# ws2812-attiny.net
KiCad netlist of a schematic drawn in EAGLE
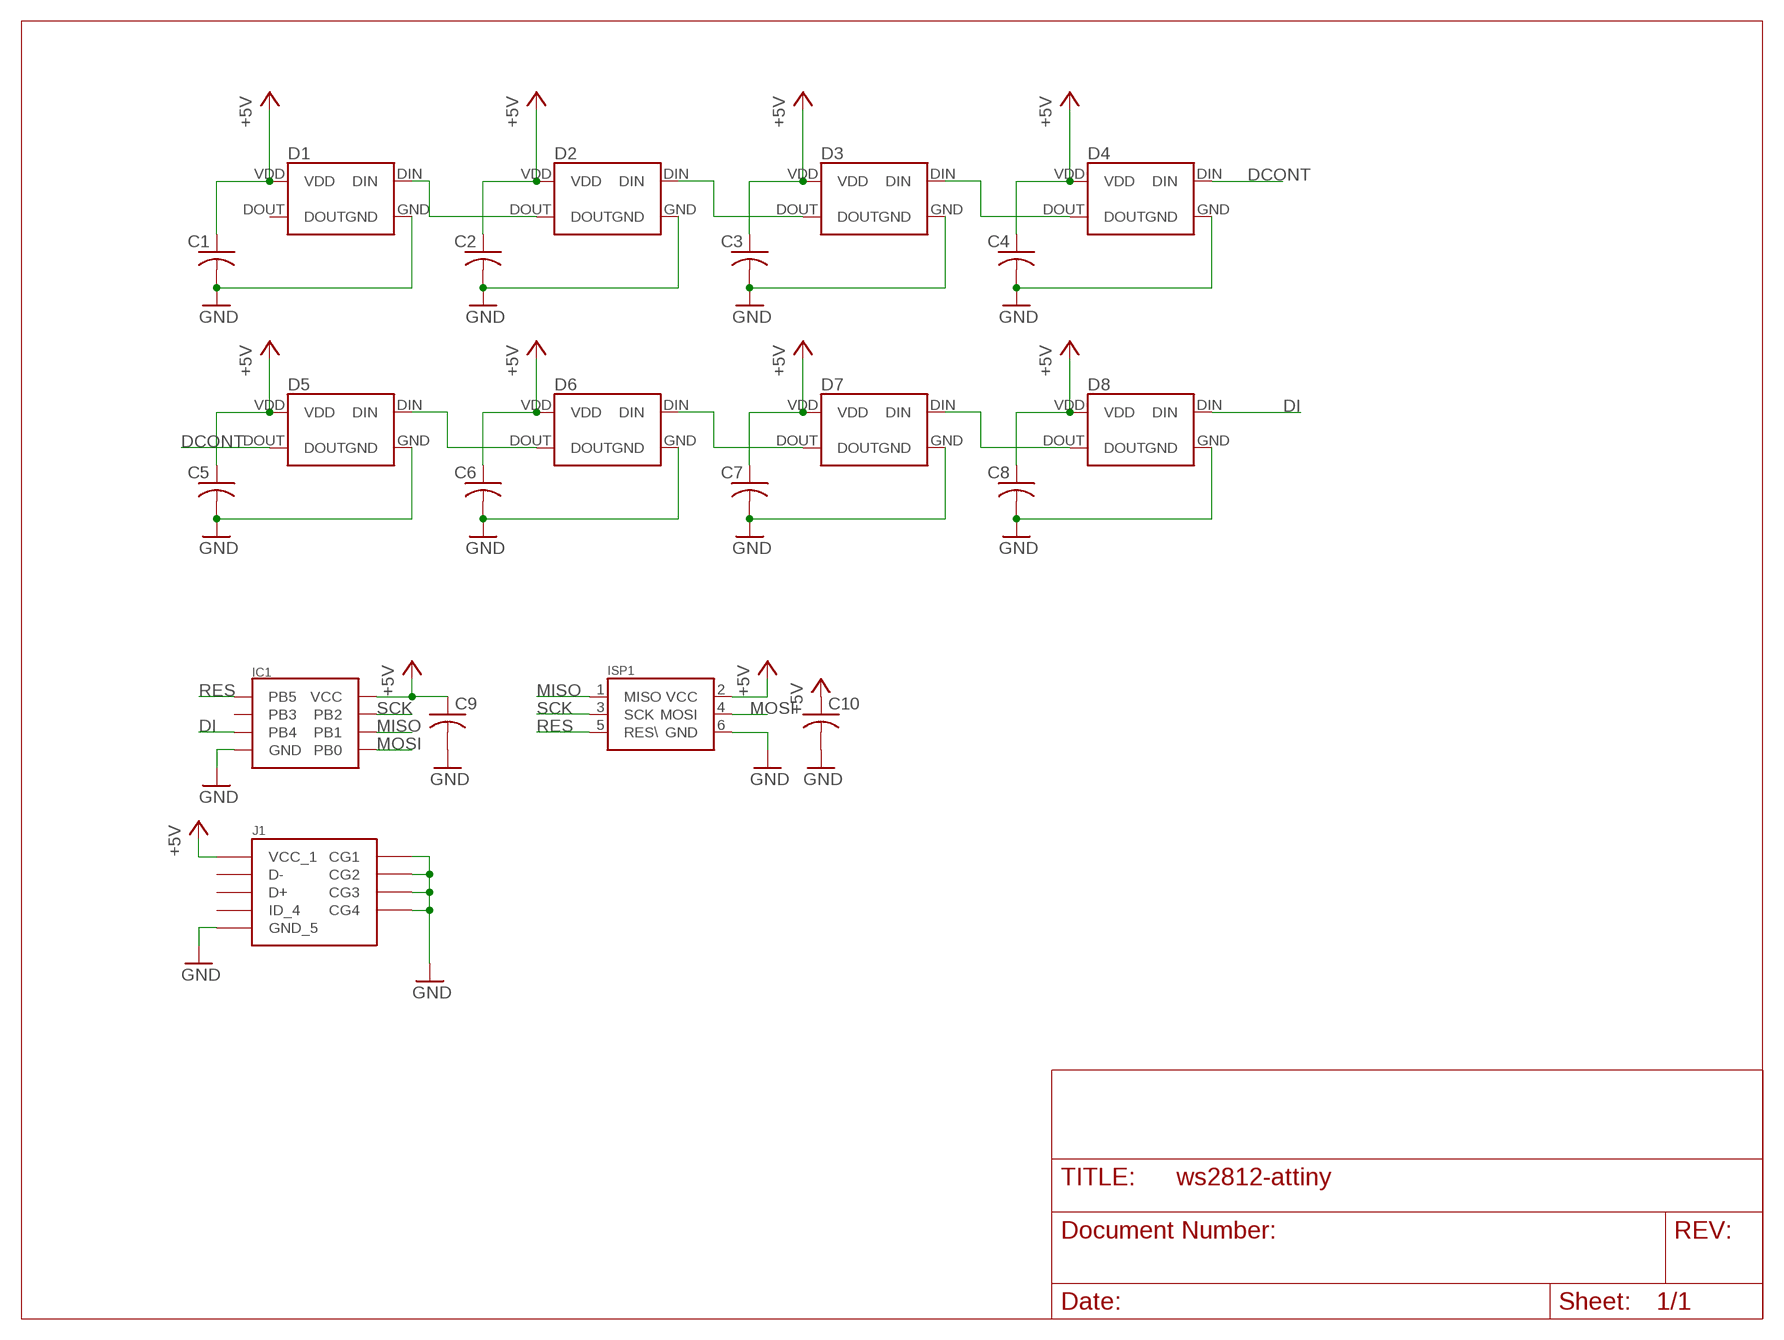
[diagram p0: schematic, sheet 1]

(export (version "E")
  (design (tool "Eeschema 10.0.6"))
  (components
    (comp (ref "C1")
      (value "C-USC1206")
      (footprint "eagle-import:C1206")
      (libsource (lib "eagle-import") (part "C-USC1206"))
    )
    (comp (ref "C2")
      (value "C-USC1206")
      (footprint "eagle-import:C1206")
      (libsource (lib "eagle-import") (part "C-USC1206"))
    )
    (comp (ref "C3")
      (value "C-USC1206")
      (footprint "eagle-import:C1206")
      (libsource (lib "eagle-import") (part "C-USC1206"))
    )
    (comp (ref "C4")
      (value "C-USC1206")
      (footprint "eagle-import:C1206")
      (libsource (lib "eagle-import") (part "C-USC1206"))
    )
    (comp (ref "C5")
      (value "C-USC1206")
      (footprint "eagle-import:C1206")
      (libsource (lib "eagle-import") (part "C-USC1206"))
    )
    (comp (ref "C6")
      (value "C-USC1206")
      (footprint "eagle-import:C1206")
      (libsource (lib "eagle-import") (part "C-USC1206"))
    )
    (comp (ref "C7")
      (value "C-USC1206")
      (footprint "eagle-import:C1206")
      (libsource (lib "eagle-import") (part "C-USC1206"))
    )
    (comp (ref "C8")
      (value "C-USC1206")
      (footprint "eagle-import:C1206")
      (libsource (lib "eagle-import") (part "C-USC1206"))
    )
    (comp (ref "C9")
      (value "C-USC1206")
      (footprint "eagle-import:C1206")
      (libsource (lib "eagle-import") (part "C-USC1206"))
    )
    (comp (ref "C10")
      (value "C-USC1206")
      (footprint "eagle-import:C1206")
      (libsource (lib "eagle-import") (part "C-USC1206"))
    )
    (comp (ref "D1")
      (value "WS2812B")
      (footprint "eagle-import:WS2812B")
      (libsource (lib "eagle-import") (part "WS2812B"))
    )
    (comp (ref "D2")
      (value "WS2812B")
      (footprint "eagle-import:WS2812B")
      (libsource (lib "eagle-import") (part "WS2812B"))
    )
    (comp (ref "D3")
      (value "WS2812B")
      (footprint "eagle-import:WS2812B")
      (libsource (lib "eagle-import") (part "WS2812B"))
    )
    (comp (ref "D4")
      (value "WS2812B")
      (footprint "eagle-import:WS2812B")
      (libsource (lib "eagle-import") (part "WS2812B"))
    )
    (comp (ref "D5")
      (value "WS2812B")
      (footprint "eagle-import:WS2812B")
      (libsource (lib "eagle-import") (part "WS2812B"))
    )
    (comp (ref "D6")
      (value "WS2812B")
      (footprint "eagle-import:WS2812B")
      (libsource (lib "eagle-import") (part "WS2812B"))
    )
    (comp (ref "D7")
      (value "WS2812B")
      (footprint "eagle-import:WS2812B")
      (libsource (lib "eagle-import") (part "WS2812B"))
    )
    (comp (ref "D8")
      (value "WS2812B")
      (footprint "eagle-import:WS2812B")
      (libsource (lib "eagle-import") (part "WS2812B"))
    )
    (comp (ref "IC1")
      (value "ATTINY85")
      (footprint "eagle-import:ATTINY-8S2")
      (libsource (lib "eagle-import") (part "ATTINY85"))
    )
    (comp (ref "ISP1")
      (value "ISP-HEADER")
      (footprint "eagle-import:2X03")
      (libsource (lib "eagle-import") (part "ISP-HEADER"))
    )
    (comp (ref "J1")
      (value "USB_JAE_DX4R005HJ5R2000")
      (footprint "eagle-import:USB_JAE_DX4R005HJ5R2000")
      (libsource (lib "eagle-import") (part "USB_JAE_DX4R005HJ5R2000"))
    )
  )
  (nets
    (net (code "1") (name "+5V") (class "Default")
      (node (ref "C1") (pin "1") (pinfunction "1_1") (pintype "passive"))
      (node (ref "C10") (pin "1") (pinfunction "1_1") (pintype "passive"))
      (node (ref "C2") (pin "1") (pinfunction "1_1") (pintype "passive"))
      (node (ref "C3") (pin "1") (pinfunction "1_1") (pintype "passive"))
      (node (ref "C4") (pin "1") (pinfunction "1_1") (pintype "passive"))
      (node (ref "C5") (pin "1") (pinfunction "1_1") (pintype "passive"))
      (node (ref "C6") (pin "1") (pinfunction "1_1") (pintype "passive"))
      (node (ref "C7") (pin "1") (pinfunction "1_1") (pintype "passive"))
      (node (ref "C8") (pin "1") (pinfunction "1_1") (pintype "passive"))
      (node (ref "C9") (pin "1") (pinfunction "1_1") (pintype "passive"))
      (node (ref "D1") (pin "VDD") (pinfunction "VDD_VDD") (pintype "bidirectional"))
      (node (ref "D2") (pin "VDD") (pinfunction "VDD_VDD") (pintype "bidirectional"))
      (node (ref "D3") (pin "VDD") (pinfunction "VDD_VDD") (pintype "bidirectional"))
      (node (ref "D4") (pin "VDD") (pinfunction "VDD_VDD") (pintype "bidirectional"))
      (node (ref "D5") (pin "VDD") (pinfunction "VDD_VDD") (pintype "bidirectional"))
      (node (ref "D6") (pin "VDD") (pinfunction "VDD_VDD") (pintype "bidirectional"))
      (node (ref "D7") (pin "VDD") (pinfunction "VDD_VDD") (pintype "bidirectional"))
      (node (ref "D8") (pin "VDD") (pinfunction "VDD_VDD") (pintype "bidirectional"))
      (node (ref "IC1") (pin "8") (pinfunction "VCC_8") (pintype "bidirectional"))
      (node (ref "ISP1") (pin "2") (pinfunction "VCC_2") (pintype "bidirectional"))
      (node (ref "J1") (pin "P$1") (pinfunction "VCC_1_P$1") (pintype "bidirectional"))
    )
    (net (code "2") (name "/DCONT") (class "Default")
      (node (ref "D4") (pin "DIN") (pinfunction "DIN_DIN") (pintype "bidirectional"))
      (node (ref "D5") (pin "DOUT") (pinfunction "DOUT_DOUT") (pintype "bidirectional"))
    )
    (net (code "3") (name "/DI") (class "Default")
      (node (ref "D8") (pin "DIN") (pinfunction "DIN_DIN") (pintype "bidirectional"))
      (node (ref "IC1") (pin "3") (pinfunction "PB4_3") (pintype "bidirectional"))
    )
    (net (code "4") (name "/MISO") (class "Default")
      (node (ref "IC1") (pin "6") (pinfunction "PB1_6") (pintype "bidirectional"))
      (node (ref "ISP1") (pin "1") (pinfunction "MISO_1") (pintype "bidirectional"))
    )
    (net (code "5") (name "/MOSI") (class "Default")
      (node (ref "IC1") (pin "5") (pinfunction "PB0_5") (pintype "bidirectional"))
      (node (ref "ISP1") (pin "4") (pinfunction "MOSI_4") (pintype "bidirectional"))
    )
    (net (code "6") (name "/RES") (class "Default")
      (node (ref "IC1") (pin "1") (pinfunction "PB5_1") (pintype "bidirectional"))
      (node (ref "ISP1") (pin "5") (pinfunction "RES\\_5") (pintype "bidirectional"))
    )
    (net (code "7") (name "/SCK") (class "Default")
      (node (ref "IC1") (pin "7") (pinfunction "PB2_7") (pintype "bidirectional"))
      (node (ref "ISP1") (pin "3") (pinfunction "SCK_3") (pintype "bidirectional"))
    )
    (net (code "8") (name "GND") (class "Default")
      (node (ref "C1") (pin "2") (pinfunction "2_2") (pintype "passive"))
      (node (ref "C10") (pin "2") (pinfunction "2_2") (pintype "passive"))
      (node (ref "C2") (pin "2") (pinfunction "2_2") (pintype "passive"))
      (node (ref "C3") (pin "2") (pinfunction "2_2") (pintype "passive"))
      (node (ref "C4") (pin "2") (pinfunction "2_2") (pintype "passive"))
      (node (ref "C5") (pin "2") (pinfunction "2_2") (pintype "passive"))
      (node (ref "C6") (pin "2") (pinfunction "2_2") (pintype "passive"))
      (node (ref "C7") (pin "2") (pinfunction "2_2") (pintype "passive"))
      (node (ref "C8") (pin "2") (pinfunction "2_2") (pintype "passive"))
      (node (ref "C9") (pin "2") (pinfunction "2_2") (pintype "passive"))
      (node (ref "D1") (pin "GND") (pinfunction "GND_GND") (pintype "bidirectional"))
      (node (ref "D2") (pin "GND") (pinfunction "GND_GND") (pintype "bidirectional"))
      (node (ref "D3") (pin "GND") (pinfunction "GND_GND") (pintype "bidirectional"))
      (node (ref "D4") (pin "GND") (pinfunction "GND_GND") (pintype "bidirectional"))
      (node (ref "D5") (pin "GND") (pinfunction "GND_GND") (pintype "bidirectional"))
      (node (ref "D6") (pin "GND") (pinfunction "GND_GND") (pintype "bidirectional"))
      (node (ref "D7") (pin "GND") (pinfunction "GND_GND") (pintype "bidirectional"))
      (node (ref "D8") (pin "GND") (pinfunction "GND_GND") (pintype "bidirectional"))
      (node (ref "IC1") (pin "4") (pinfunction "GND_4") (pintype "bidirectional"))
      (node (ref "ISP1") (pin "6") (pinfunction "GND_6") (pintype "bidirectional"))
      (node (ref "J1") (pin "P$5") (pinfunction "GND_5_P$5") (pintype "bidirectional"))
      (node (ref "J1") (pin "P$6") (pinfunction "CG4_P$6") (pintype "bidirectional"))
      (node (ref "J1") (pin "P$7") (pinfunction "CG3_P$7") (pintype "bidirectional"))
      (node (ref "J1") (pin "P$8") (pinfunction "CG2_P$8") (pintype "bidirectional"))
      (node (ref "J1") (pin "P$9") (pinfunction "CG1_P$9") (pintype "bidirectional"))
    )
    (net (code "9") (name "Net-(D1-PadDIN)") (class "Default")
      (node (ref "D1") (pin "DIN") (pinfunction "DIN_DIN") (pintype "bidirectional"))
      (node (ref "D2") (pin "DOUT") (pinfunction "DOUT_DOUT") (pintype "bidirectional"))
    )
    (net (code "10") (name "Net-(D2-PadDIN)") (class "Default")
      (node (ref "D2") (pin "DIN") (pinfunction "DIN_DIN") (pintype "bidirectional"))
      (node (ref "D3") (pin "DOUT") (pinfunction "DOUT_DOUT") (pintype "bidirectional"))
    )
    (net (code "11") (name "Net-(D3-PadDIN)") (class "Default")
      (node (ref "D3") (pin "DIN") (pinfunction "DIN_DIN") (pintype "bidirectional"))
      (node (ref "D4") (pin "DOUT") (pinfunction "DOUT_DOUT") (pintype "bidirectional"))
    )
    (net (code "12") (name "Net-(D5-PadDIN)") (class "Default")
      (node (ref "D5") (pin "DIN") (pinfunction "DIN_DIN") (pintype "bidirectional"))
      (node (ref "D6") (pin "DOUT") (pinfunction "DOUT_DOUT") (pintype "bidirectional"))
    )
    (net (code "13") (name "Net-(D6-PadDIN)") (class "Default")
      (node (ref "D6") (pin "DIN") (pinfunction "DIN_DIN") (pintype "bidirectional"))
      (node (ref "D7") (pin "DOUT") (pinfunction "DOUT_DOUT") (pintype "bidirectional"))
    )
    (net (code "14") (name "Net-(D7-PadDIN)") (class "Default")
      (node (ref "D7") (pin "DIN") (pinfunction "DIN_DIN") (pintype "bidirectional"))
      (node (ref "D8") (pin "DOUT") (pinfunction "DOUT_DOUT") (pintype "bidirectional"))
    )
    (net (code "15") (name "unconnected-(D1-PadDOUT)") (class "Default")
      (node (ref "D1") (pin "DOUT") (pinfunction "DOUT_DOUT") (pintype "bidirectional"))
    )
    (net (code "16") (name "unconnected-(IC1-PB3-Pad2)") (class "Default")
      (node (ref "IC1") (pin "2") (pinfunction "PB3_2") (pintype "bidirectional"))
    )
    (net (code "17") (name "unconnected-(J1-D+-PadP$3)") (class "Default")
      (node (ref "J1") (pin "P$3") (pinfunction "D+_P$3") (pintype "bidirectional"))
    )
    (net (code "18") (name "unconnected-(J1-D--PadP$2)") (class "Default")
      (node (ref "J1") (pin "P$2") (pinfunction "D-_P$2") (pintype "bidirectional"))
    )
    (net (code "19") (name "unconnected-(J1-ID_4-PadP$4)") (class "Default")
      (node (ref "J1") (pin "P$4") (pinfunction "ID_4_P$4") (pintype "bidirectional"))
    )
  )
)
